# Battery_Board_v1.net
KiCad netlist of a schematic drawn in EAGLE
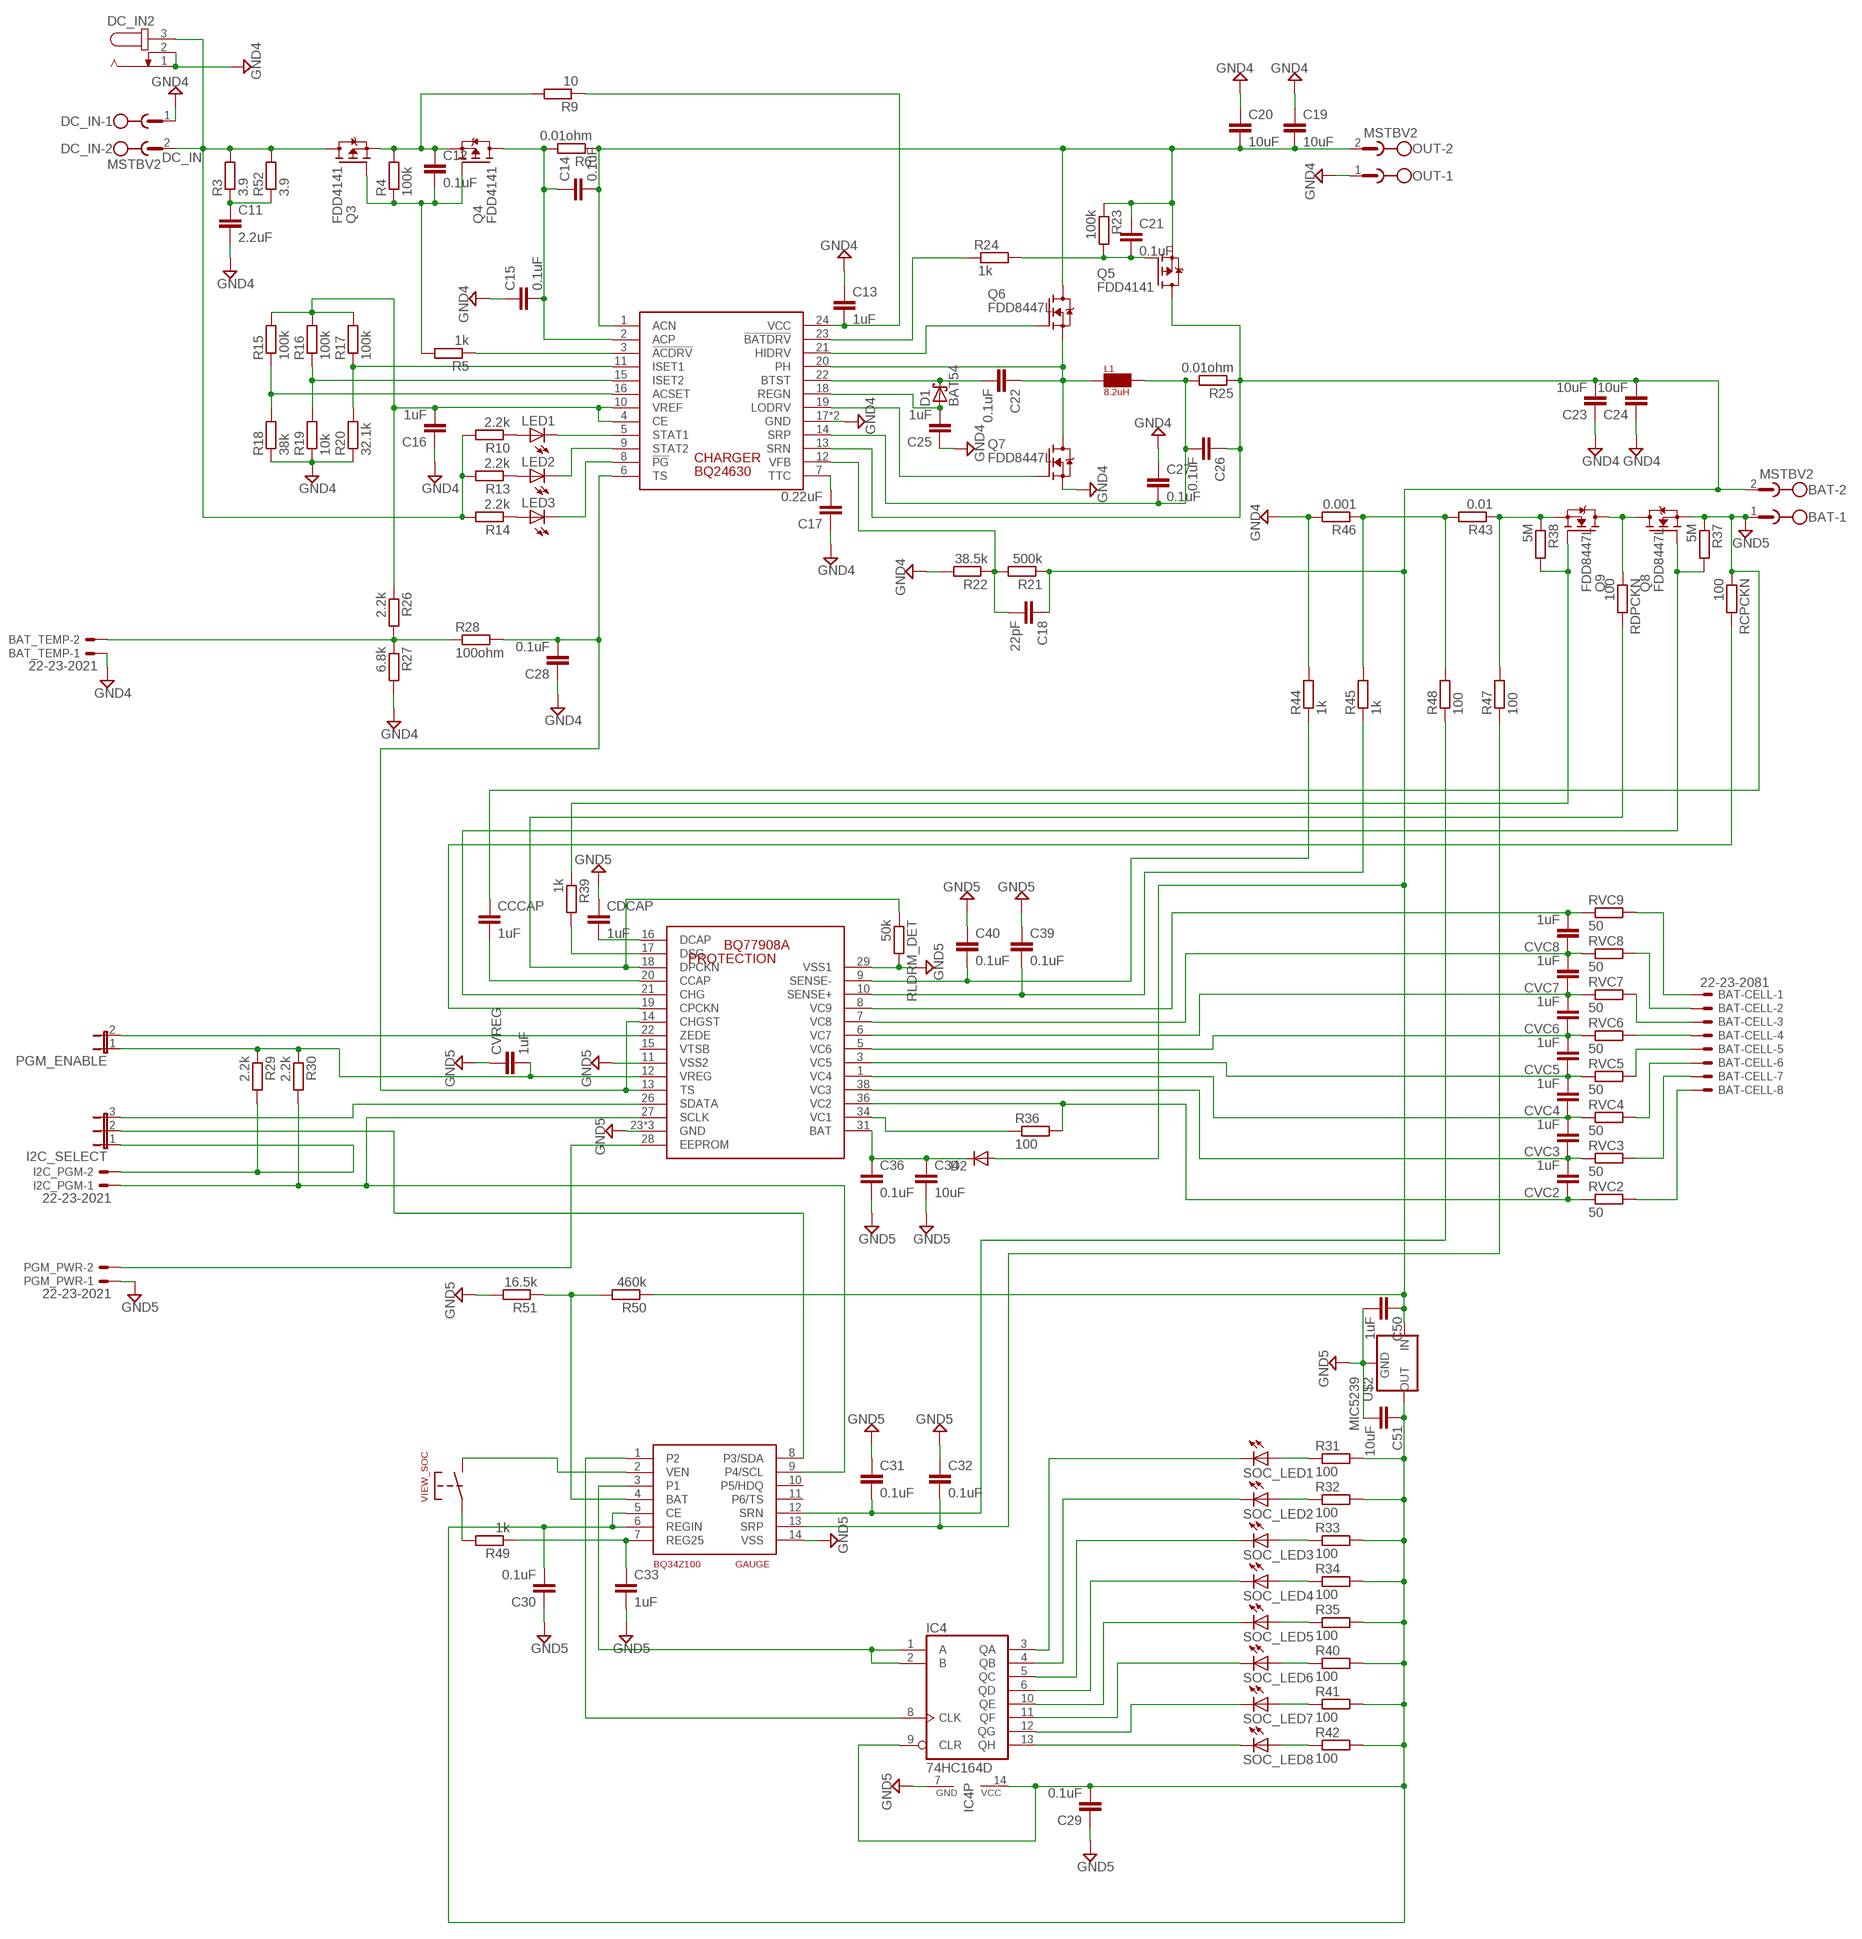
[diagram p0: schematic, sheet 1]

(export (version "E")
  (design (tool "Eeschema 10.0.6"))
  (components
    (comp (ref "BAT")
      (value "MSTBV2")
      (footprint "eagle-import:MSTBV2")
      (fields
        (field (name "MPN") "MSTBV 2,5/2-GF-5.08")
        (field (name "MPN_1") "MSTBV 2,5/2-GF-5.08")
        (field (name "OC_FARNELL") "1792792")
        (field (name "OC_NEWARK") "69R9845")
      )
      (libsource (lib "eagle-import") (part "MSTBV2"))
    )
    (comp (ref "BAT-CELL")
      (value "22-23-2081")
      (footprint "eagle-import:22-23-2081")
      (fields (field (name "MF") "MOLEX"))
      (libsource (lib "eagle-import") (part "22-23-2081"))
    )
    (comp (ref "BAT_TEMP")
      (value "22-23-2021")
      (footprint "eagle-import:22-23-2021")
      (fields
        (field (name "MF") "MOLEX")
        (field (name "MF_1") "MOLEX")
        (field (name "MPN") "22-23-2021")
        (field (name "OC_FARNELL") "1462926")
        (field (name "OC_NEWARK") "25C3832")
      )
      (libsource (lib "eagle-import") (part "22-23-2021"))
    )
    (comp (ref "C11")
      (value "2.2uF")
      (footprint "eagle-import:C1206")
      (libsource (lib "eagle-import") (part "C-EUC1206"))
    )
    (comp (ref "C12")
      (value "0.1uF")
      (footprint "eagle-import:C0603")
      (libsource (lib "eagle-import") (part "C-EUC0603"))
    )
    (comp (ref "C13")
      (value "1uF")
      (footprint "eagle-import:C1206")
      (libsource (lib "eagle-import") (part "C-EUC1206"))
    )
    (comp (ref "C14")
      (value "0.1uF")
      (footprint "eagle-import:C0603")
      (libsource (lib "eagle-import") (part "C-EUC0603"))
    )
    (comp (ref "C15")
      (value "0.1uF")
      (footprint "eagle-import:C0603")
      (libsource (lib "eagle-import") (part "C-EUC0603"))
    )
    (comp (ref "C16")
      (value "1uF")
      (footprint "eagle-import:C0805")
      (libsource (lib "eagle-import") (part "C-EUC0805"))
    )
    (comp (ref "C17")
      (value "0.22uF")
      (footprint "eagle-import:C0603")
      (libsource (lib "eagle-import") (part "C-EUC0603"))
    )
    (comp (ref "C18")
      (value "22pF")
      (footprint "eagle-import:C0603")
      (libsource (lib "eagle-import") (part "C-EUC0603"))
    )
    (comp (ref "C19")
      (value "10uF")
      (footprint "eagle-import:C1812")
      (libsource (lib "eagle-import") (part "C-EUC1812"))
    )
    (comp (ref "C20")
      (value "10uF")
      (footprint "eagle-import:C1812")
      (libsource (lib "eagle-import") (part "C-EUC1812"))
    )
    (comp (ref "C21")
      (value "0.1uF")
      (footprint "eagle-import:C0603")
      (libsource (lib "eagle-import") (part "C-EUC0603"))
    )
    (comp (ref "C22")
      (value "0.1uF")
      (footprint "eagle-import:C0603")
      (libsource (lib "eagle-import") (part "C-EUC0603"))
    )
    (comp (ref "C23")
      (value "10uF")
      (footprint "eagle-import:C1812")
      (libsource (lib "eagle-import") (part "C-EUC1812"))
    )
    (comp (ref "C24")
      (value "10uF")
      (footprint "eagle-import:C1812")
      (libsource (lib "eagle-import") (part "C-EUC1812"))
    )
    (comp (ref "C25")
      (value "1uF")
      (footprint "eagle-import:C0805")
      (libsource (lib "eagle-import") (part "C-EUC0805"))
    )
    (comp (ref "C26")
      (value "0.1uF")
      (footprint "eagle-import:C0603")
      (libsource (lib "eagle-import") (part "C-EUC0603"))
    )
    (comp (ref "C27")
      (value "0.1uF")
      (footprint "eagle-import:C0603")
      (libsource (lib "eagle-import") (part "C-EUC0603"))
    )
    (comp (ref "C28")
      (value "0.1uF")
      (footprint "eagle-import:C0603")
      (libsource (lib "eagle-import") (part "C-EUC0603"))
    )
    (comp (ref "C29")
      (value "0.1uF")
      (footprint "eagle-import:C0603")
      (libsource (lib "eagle-import") (part "C-EUC0603"))
    )
    (comp (ref "C30")
      (value "0.1uF")
      (footprint "eagle-import:C0603")
      (libsource (lib "eagle-import") (part "C-EUC0603"))
    )
    (comp (ref "C31")
      (value "0.1uF")
      (footprint "eagle-import:C0603")
      (libsource (lib "eagle-import") (part "C-EUC0603"))
    )
    (comp (ref "C32")
      (value "0.1uF")
      (footprint "eagle-import:C0603")
      (libsource (lib "eagle-import") (part "C-EUC0603"))
    )
    (comp (ref "C33")
      (value "1uF")
      (footprint "eagle-import:C0603")
      (libsource (lib "eagle-import") (part "C-EUC0603"))
    )
    (comp (ref "C34")
      (value "10uF")
      (footprint "eagle-import:C1210")
      (libsource (lib "eagle-import") (part "C-EUC1210"))
    )
    (comp (ref "C36")
      (value "0.1uF")
      (footprint "eagle-import:C1210")
      (libsource (lib "eagle-import") (part "C-EUC1210"))
    )
    (comp (ref "C39")
      (value "0.1uF")
      (footprint "eagle-import:C0603")
      (libsource (lib "eagle-import") (part "C-EUC0603"))
    )
    (comp (ref "C40")
      (value "0.1uF")
      (footprint "eagle-import:C0603")
      (libsource (lib "eagle-import") (part "C-EUC0603"))
    )
    (comp (ref "C50")
      (value "1uF")
      (footprint "eagle-import:C0603")
      (libsource (lib "eagle-import") (part "C-EUC0603"))
    )
    (comp (ref "C51")
      (value "10uF")
      (footprint "eagle-import:C0603")
      (libsource (lib "eagle-import") (part "C-EUC0603"))
    )
    (comp (ref "CCCAP")
      (value "1uF")
      (footprint "eagle-import:C1206")
      (libsource (lib "eagle-import") (part "C-EUC1206"))
    )
    (comp (ref "CDCAP")
      (value "1uF")
      (footprint "eagle-import:C1206")
      (libsource (lib "eagle-import") (part "C-EUC1206"))
    )
    (comp (ref "CHARGER")
      (value "BQ24630")
      (footprint "eagle-import:QFN-24")
      (libsource (lib "eagle-import") (part "BQ24630"))
    )
    (comp (ref "CVC2")
      (value "1uF")
      (footprint "eagle-import:C0603")
      (libsource (lib "eagle-import") (part "C-EUC0603"))
    )
    (comp (ref "CVC3")
      (value "1uF")
      (footprint "eagle-import:C0603")
      (libsource (lib "eagle-import") (part "C-EUC0603"))
    )
    (comp (ref "CVC4")
      (value "1uF")
      (footprint "eagle-import:C0603")
      (libsource (lib "eagle-import") (part "C-EUC0603"))
    )
    (comp (ref "CVC5")
      (value "1uF")
      (footprint "eagle-import:C0603")
      (libsource (lib "eagle-import") (part "C-EUC0603"))
    )
    (comp (ref "CVC6")
      (value "1uF")
      (footprint "eagle-import:C0603")
      (libsource (lib "eagle-import") (part "C-EUC0603"))
    )
    (comp (ref "CVC7")
      (value "1uF")
      (footprint "eagle-import:C0603")
      (libsource (lib "eagle-import") (part "C-EUC0603"))
    )
    (comp (ref "CVC8")
      (value "1uF")
      (footprint "eagle-import:C0603")
      (libsource (lib "eagle-import") (part "C-EUC0603"))
    )
    (comp (ref "CVREG")
      (value "1uF")
      (footprint "eagle-import:C0603")
      (libsource (lib "eagle-import") (part "C-EUC0603"))
    )
    (comp (ref "D1")
      (value "BAT54")
      (footprint "eagle-import:SOT23")
      (libsource (lib "eagle-import") (part "BAT54"))
    )
    (comp (ref "D2")
      (value "DIODE-SOD123")
      (footprint "eagle-import:SOD123")
      (libsource (lib "eagle-import") (part "DIODE-SOD123"))
    )
    (comp (ref "DC_IN")
      (value "MSTBV2")
      (footprint "eagle-import:MSTBV2")
      (fields (field (name "MPN") "MSTBV 2,5/2-GF-5.08"))
      (libsource (lib "eagle-import") (part "MSTBV2"))
    )
    (comp (ref "DC_IN2")
      (value "JACK-PLUG1")
      (footprint "eagle-import:SPC4078")
      (libsource (lib "eagle-import") (part "JACK-PLUG1"))
    )
    (comp (ref "GAUGE")
      (value "BQ34Z100")
      (footprint "eagle-import:TSSOP-14-0.65MM")
      (libsource (lib "eagle-import") (part "BQ34Z100"))
    )
    (comp (ref "I2C_PGM")
      (value "22-23-2021")
      (footprint "eagle-import:22-23-2021")
      (fields
        (field (name "MF") "MOLEX")
        (field (name "MF_1") "MOLEX")
        (field (name "MPN") "22-23-2021")
        (field (name "OC_FARNELL") "1462926")
        (field (name "OC_NEWARK") "25C3832")
      )
      (libsource (lib "eagle-import") (part "22-23-2021"))
    )
    (comp (ref "I2C_SELECT")
      (value "JP2E")
      (footprint "eagle-import:JP2")
      (libsource (lib "eagle-import") (part "JP2E"))
    )
    (comp (ref "IC4")
      (value "74HC164D")
      (footprint "eagle-import:SO14")
      (libsource (lib "eagle-import") (part "74164DHC"))
    )
    (comp (ref "L1")
      (value "8.2uH")
      (footprint "eagle-import:5050CE")
      (libsource (lib "eagle-import") (part "IHLP-5050CE"))
    )
    (comp (ref "LED1")
      (value "LEDCHIP-LED0603")
      (footprint "eagle-import:CHIP-LED0603")
      (libsource (lib "eagle-import") (part "LEDCHIP-LED0603"))
    )
    (comp (ref "LED2")
      (value "LEDCHIP-LED0603")
      (footprint "eagle-import:CHIP-LED0603")
      (libsource (lib "eagle-import") (part "LEDCHIP-LED0603"))
    )
    (comp (ref "LED3")
      (value "LEDCHIP-LED0603")
      (footprint "eagle-import:CHIP-LED0603")
      (libsource (lib "eagle-import") (part "LEDCHIP-LED0603"))
    )
    (comp (ref "OUT")
      (value "MSTBV2")
      (footprint "eagle-import:MSTBV2")
      (fields
        (field (name "MPN") "MSTBV 2,5/2-GF-5.08")
        (field (name "MPN_1") "MSTBV 2,5/2-GF-5.08")
        (field (name "OC_FARNELL") "1792792")
        (field (name "OC_NEWARK") "69R9845")
      )
      (libsource (lib "eagle-import") (part "MSTBV2"))
    )
    (comp (ref "PGM_ENABLE")
      (value "JP1E")
      (footprint "eagle-import:JP1")
      (libsource (lib "eagle-import") (part "JP1E"))
    )
    (comp (ref "PGM_PWR")
      (value "22-23-2021")
      (footprint "eagle-import:22-23-2021")
      (fields
        (field (name "MF") "MOLEX")
        (field (name "MF_1") "MOLEX")
        (field (name "MPN") "22-23-2021")
        (field (name "OC_FARNELL") "1462926")
        (field (name "OC_NEWARK") "25C3832")
      )
      (libsource (lib "eagle-import") (part "22-23-2021"))
    )
    (comp (ref "PROTECTION")
      (value "BQ77908A")
      (footprint "eagle-import:TSSOP-38-0.5MM")
      (libsource (lib "eagle-import") (part "BQ77908A"))
    )
    (comp (ref "Q3")
      (value "FDD4141")
      (footprint "eagle-import:TO252")
      (libsource (lib "eagle-import") (part "FDD4141TO252"))
    )
    (comp (ref "Q4")
      (value "FDD4141")
      (footprint "eagle-import:TO252")
      (libsource (lib "eagle-import") (part "FDD4141TO252"))
    )
    (comp (ref "Q5")
      (value "FDD4141")
      (footprint "eagle-import:TO252")
      (libsource (lib "eagle-import") (part "FDD4141TO252"))
    )
    (comp (ref "Q6")
      (value "FDD8447L")
      (footprint "eagle-import:TO252")
      (libsource (lib "eagle-import") (part "FDD8447L"))
    )
    (comp (ref "Q7")
      (value "FDD8447L")
      (footprint "eagle-import:TO252")
      (libsource (lib "eagle-import") (part "FDD8447L"))
    )
    (comp (ref "Q8")
      (value "FDD8447L")
      (footprint "eagle-import:TO252")
      (libsource (lib "eagle-import") (part "FDD8447L"))
    )
    (comp (ref "Q9")
      (value "FDD8447L")
      (footprint "eagle-import:TO252")
      (libsource (lib "eagle-import") (part "FDD8447L"))
    )
    (comp (ref "R3")
      (value "3.9")
      (footprint "eagle-import:R1206")
      (libsource (lib "eagle-import") (part "R-EU_R1206"))
    )
    (comp (ref "R4")
      (value "100k")
      (footprint "eagle-import:R0603")
      (libsource (lib "eagle-import") (part "R-EU_R0603"))
    )
    (comp (ref "R5")
      (value "1k")
      (footprint "eagle-import:R0603")
      (libsource (lib "eagle-import") (part "R-EU_R0603"))
    )
    (comp (ref "R6")
      (value "0.01ohm")
      (footprint "eagle-import:R2010")
      (libsource (lib "eagle-import") (part "R-EU_R2010"))
    )
    (comp (ref "R9")
      (value "10")
      (footprint "eagle-import:R1206")
      (libsource (lib "eagle-import") (part "R-EU_R1206"))
    )
    (comp (ref "R10")
      (value "2.2k")
      (footprint "eagle-import:R0603")
      (libsource (lib "eagle-import") (part "R-EU_R0603"))
    )
    (comp (ref "R13")
      (value "2.2k")
      (footprint "eagle-import:R0603")
      (libsource (lib "eagle-import") (part "R-EU_R0603"))
    )
    (comp (ref "R14")
      (value "2.2k")
      (footprint "eagle-import:R0603")
      (libsource (lib "eagle-import") (part "R-EU_R0603"))
    )
    (comp (ref "R15")
      (value "100k")
      (footprint "eagle-import:R0805")
      (libsource (lib "eagle-import") (part "R-EU_R0805"))
    )
    (comp (ref "R16")
      (value "100k")
      (footprint "eagle-import:R0805")
      (libsource (lib "eagle-import") (part "R-EU_R0805"))
    )
    (comp (ref "R17")
      (value "100k")
      (footprint "eagle-import:R0805")
      (libsource (lib "eagle-import") (part "R-EU_R0805"))
    )
    (comp (ref "R18")
      (value "38k")
      (footprint "eagle-import:R0805")
      (libsource (lib "eagle-import") (part "R-EU_R0805"))
    )
    (comp (ref "R19")
      (value "10k")
      (footprint "eagle-import:R0805")
      (libsource (lib "eagle-import") (part "R-EU_R0805"))
    )
    (comp (ref "R20")
      (value "32.1k")
      (footprint "eagle-import:R0805")
      (libsource (lib "eagle-import") (part "R-EU_R0805"))
    )
    (comp (ref "R21")
      (value "500k")
      (footprint "eagle-import:R0805")
      (libsource (lib "eagle-import") (part "R-EU_R0805"))
    )
    (comp (ref "R22")
      (value "38.5k")
      (footprint "eagle-import:R0805")
      (libsource (lib "eagle-import") (part "R-EU_R0805"))
    )
    (comp (ref "R23")
      (value "100k")
      (footprint "eagle-import:R0603")
      (libsource (lib "eagle-import") (part "R-EU_R0603"))
    )
    (comp (ref "R24")
      (value "1k")
      (footprint "eagle-import:R0603")
      (libsource (lib "eagle-import") (part "R-EU_R0603"))
    )
    (comp (ref "R25")
      (value "0.01ohm")
      (footprint "eagle-import:R2010")
      (libsource (lib "eagle-import") (part "R-EU_R2010"))
    )
    (comp (ref "R26")
      (value "2.2k")
      (footprint "eagle-import:R0603")
      (libsource (lib "eagle-import") (part "R-EU_R0603"))
    )
    (comp (ref "R27")
      (value "6.8k")
      (footprint "eagle-import:R0603")
      (libsource (lib "eagle-import") (part "R-EU_R0603"))
    )
    (comp (ref "R28")
      (value "100ohm")
      (footprint "eagle-import:R0603")
      (libsource (lib "eagle-import") (part "R-EU_R0603"))
    )
    (comp (ref "R29")
      (value "2.2k")
      (footprint "eagle-import:R0603")
      (libsource (lib "eagle-import") (part "R-EU_R0603"))
    )
    (comp (ref "R30")
      (value "2.2k")
      (footprint "eagle-import:R0603")
      (libsource (lib "eagle-import") (part "R-EU_R0603"))
    )
    (comp (ref "R31")
      (value "100")
      (footprint "eagle-import:R0603")
      (libsource (lib "eagle-import") (part "R-EU_R0603"))
    )
    (comp (ref "R32")
      (value "100")
      (footprint "eagle-import:R0603")
      (libsource (lib "eagle-import") (part "R-EU_R0603"))
    )
    (comp (ref "R33")
      (value "100")
      (footprint "eagle-import:R0603")
      (libsource (lib "eagle-import") (part "R-EU_R0603"))
    )
    (comp (ref "R34")
      (value "100")
      (footprint "eagle-import:R0603")
      (libsource (lib "eagle-import") (part "R-EU_R0603"))
    )
    (comp (ref "R35")
      (value "100")
      (footprint "eagle-import:R0603")
      (libsource (lib "eagle-import") (part "R-EU_R0603"))
    )
    (comp (ref "R36")
      (value "100")
      (footprint "eagle-import:R0603")
      (libsource (lib "eagle-import") (part "R-EU_R0603"))
    )
    (comp (ref "R37")
      (value "5M")
      (footprint "eagle-import:R0603")
      (libsource (lib "eagle-import") (part "R-EU_R0603"))
    )
    (comp (ref "R38")
      (value "5M")
      (footprint "eagle-import:R0603")
      (libsource (lib "eagle-import") (part "R-EU_R0603"))
    )
    (comp (ref "R39")
      (value "1k")
      (footprint "eagle-import:R0603")
      (libsource (lib "eagle-import") (part "R-EU_R0603"))
    )
    (comp (ref "R40")
      (value "100")
      (footprint "eagle-import:R0603")
      (libsource (lib "eagle-import") (part "R-EU_R0603"))
    )
    (comp (ref "R41")
      (value "100")
      (footprint "eagle-import:R0603")
      (libsource (lib "eagle-import") (part "R-EU_R0603"))
    )
    (comp (ref "R42")
      (value "100")
      (footprint "eagle-import:R0603")
      (libsource (lib "eagle-import") (part "R-EU_R0603"))
    )
    (comp (ref "R43")
      (value "0.01")
      (footprint "eagle-import:R2010")
      (libsource (lib "eagle-import") (part "R-EU_R2010"))
    )
    (comp (ref "R44")
      (value "1k")
      (footprint "eagle-import:R0603")
      (libsource (lib "eagle-import") (part "R-EU_R0603"))
    )
    (comp (ref "R45")
      (value "1k")
      (footprint "eagle-import:R0603")
      (libsource (lib "eagle-import") (part "R-EU_R0603"))
    )
    (comp (ref "R46")
      (value "0.001")
      (footprint "eagle-import:R2010")
      (libsource (lib "eagle-import") (part "R-EU_R2010"))
    )
    (comp (ref "R47")
      (value "100")
      (footprint "eagle-import:R0603")
      (libsource (lib "eagle-import") (part "R-EU_R0603"))
    )
    (comp (ref "R48")
      (value "100")
      (footprint "eagle-import:R0603")
      (libsource (lib "eagle-import") (part "R-EU_R0603"))
    )
    (comp (ref "R49")
      (value "1k")
      (footprint "eagle-import:R0603")
      (libsource (lib "eagle-import") (part "R-EU_R0603"))
    )
    (comp (ref "R50")
      (value "460k")
      (footprint "eagle-import:R0805")
      (libsource (lib "eagle-import") (part "R-EU_R0805"))
    )
    (comp (ref "R51")
      (value "16.5k")
      (footprint "eagle-import:R0603")
      (libsource (lib "eagle-import") (part "R-EU_R0603"))
    )
    (comp (ref "R52")
      (value "3.9")
      (footprint "eagle-import:R1206")
      (libsource (lib "eagle-import") (part "R-EU_R1206"))
    )
    (comp (ref "RCPCKN")
      (value "100")
      (footprint "eagle-import:R0603")
      (libsource (lib "eagle-import") (part "R-EU_R0603"))
    )
    (comp (ref "RDPCKN")
      (value "100")
      (footprint "eagle-import:R0603")
      (libsource (lib "eagle-import") (part "R-EU_R0603"))
    )
    (comp (ref "RLDRM_DET")
      (value "50k")
      (footprint "eagle-import:R0603")
      (libsource (lib "eagle-import") (part "R-EU_R0603"))
    )
    (comp (ref "RVC2")
      (value "50")
      (footprint "eagle-import:R1206")
      (libsource (lib "eagle-import") (part "R-EU_R1206"))
    )
    (comp (ref "RVC3")
      (value "50")
      (footprint "eagle-import:R1206")
      (libsource (lib "eagle-import") (part "R-EU_R1206"))
    )
    (comp (ref "RVC4")
      (value "50")
      (footprint "eagle-import:R1206")
      (libsource (lib "eagle-import") (part "R-EU_R1206"))
    )
    (comp (ref "RVC5")
      (value "50")
      (footprint "eagle-import:R1206")
      (libsource (lib "eagle-import") (part "R-EU_R1206"))
    )
    (comp (ref "RVC6")
      (value "50")
      (footprint "eagle-import:R1206")
      (libsource (lib "eagle-import") (part "R-EU_R1206"))
    )
    (comp (ref "RVC7")
      (value "50")
      (footprint "eagle-import:R1206")
      (libsource (lib "eagle-import") (part "R-EU_R1206"))
    )
    (comp (ref "RVC8")
      (value "50")
      (footprint "eagle-import:R1206")
      (libsource (lib "eagle-import") (part "R-EU_R1206"))
    )
    (comp (ref "RVC9")
      (value "50")
      (footprint "eagle-import:R1206")
      (libsource (lib "eagle-import") (part "R-EU_R1206"))
    )
    (comp (ref "SOC_LED1")
      (value "LEDCHIP-LED0603")
      (footprint "eagle-import:CHIP-LED0603")
      (libsource (lib "eagle-import") (part "LEDCHIP-LED0603"))
    )
    (comp (ref "SOC_LED2")
      (value "LEDCHIP-LED0603")
      (footprint "eagle-import:CHIP-LED0603")
      (libsource (lib "eagle-import") (part "LEDCHIP-LED0603"))
    )
    (comp (ref "SOC_LED3")
      (value "LEDCHIP-LED0603")
      (footprint "eagle-import:CHIP-LED0603")
      (libsource (lib "eagle-import") (part "LEDCHIP-LED0603"))
    )
    (comp (ref "SOC_LED4")
      (value "LEDCHIP-LED0603")
      (footprint "eagle-import:CHIP-LED0603")
      (libsource (lib "eagle-import") (part "LEDCHIP-LED0603"))
    )
    (comp (ref "SOC_LED5")
      (value "LEDCHIP-LED0603")
      (footprint "eagle-import:CHIP-LED0603")
      (libsource (lib "eagle-import") (part "LEDCHIP-LED0603"))
    )
    (comp (ref "SOC_LED6")
      (value "LEDCHIP-LED0603")
      (footprint "eagle-import:CHIP-LED0603")
      (libsource (lib "eagle-import") (part "LEDCHIP-LED0603"))
    )
    (comp (ref "SOC_LED7")
      (value "LEDCHIP-LED0603")
      (footprint "eagle-import:CHIP-LED0603")
      (libsource (lib "eagle-import") (part "LEDCHIP-LED0603"))
    )
    (comp (ref "SOC_LED8")
      (value "LEDCHIP-LED0603")
      (footprint "eagle-import:CHIP-LED0603")
      (libsource (lib "eagle-import") (part "LEDCHIP-LED0603"))
    )
    (comp (ref "U$2")
      (value "MIC5239")
      (footprint "eagle-import:SOT223")
      (libsource (lib "eagle-import") (part "MIC5239"))
    )
    (comp (ref "VIEW_SOC")
      (value "PUSHBUTTON")
      (footprint "eagle-import:PUSHBUTTON")
      (libsource (lib "eagle-import") (part "PUSHBUTTON"))
    )
  )
  (nets
    (net (code "1") (name "/DC_IN") (class "Default")
      (node (ref "DC_IN") (pin "2") (pinfunction "1_2") (pintype "passive"))
      (node (ref "DC_IN2") (pin "3") (pinfunction "3_3") (pintype "passive"))
      (node (ref "Q3") (pin "3") (pinfunction "D_3") (pintype "passive"))
      (node (ref "R10") (pin "2") (pinfunction "2_2") (pintype "passive"))
      (node (ref "R13") (pin "2") (pinfunction "2_2") (pintype "passive"))
      (node (ref "R14") (pin "2") (pinfunction "2_2") (pintype "passive"))
      (node (ref "R3") (pin "2") (pinfunction "2_2") (pintype "passive"))
      (node (ref "R52") (pin "2") (pinfunction "2_2") (pintype "passive"))
    )
    (net (code "2") (name "GND4") (class "Default")
      (node (ref "BAT_TEMP") (pin "1") (pinfunction "S_1") (pintype "passive"))
      (node (ref "C11") (pin "2") (pinfunction "2_2") (pintype "passive"))
      (node (ref "C13") (pin "1") (pinfunction "1_1") (pintype "passive"))
      (node (ref "C15") (pin "1") (pinfunction "1_1") (pintype "passive"))
      (node (ref "C16") (pin "1") (pinfunction "1_1") (pintype "passive"))
      (node (ref "C17") (pin "1") (pinfunction "1_1") (pintype "passive"))
      (node (ref "C19") (pin "1") (pinfunction "1_1") (pintype "passive"))
      (node (ref "C20") (pin "1") (pinfunction "1_1") (pintype "passive"))
      (node (ref "C23") (pin "1") (pinfunction "1_1") (pintype "passive"))
      (node (ref "C24") (pin "1") (pinfunction "1_1") (pintype "passive"))
      (node (ref "C25") (pin "1") (pinfunction "1_1") (pintype "passive"))
      (node (ref "C27") (pin "1") (pinfunction "1_1") (pintype "passive"))
      (node (ref "C28") (pin "1") (pinfunction "1_1") (pintype "passive"))
      (node (ref "CHARGER") (pin "17") (pinfunction "GND_17") (pintype "bidirectional"))
      (node (ref "CHARGER") (pin "THERMAL") (pinfunction "GND_THERMAL") (pintype "bidirectional"))
      (node (ref "DC_IN") (pin "1") (pinfunction "1_1") (pintype "passive"))
      (node (ref "DC_IN2") (pin "1") (pinfunction "1_1") (pintype "passive"))
      (node (ref "DC_IN2") (pin "2") (pinfunction "2_2") (pintype "passive"))
      (node (ref "OUT") (pin "1") (pinfunction "1_1") (pintype "passive"))
      (node (ref "Q7") (pin "2") (pinfunction "S_2") (pintype "passive"))
      (node (ref "R18") (pin "1") (pinfunction "1_1") (pintype "passive"))
      (node (ref "R19") (pin "1") (pinfunction "1_1") (pintype "passive"))
      (node (ref "R20") (pin "1") (pinfunction "1_1") (pintype "passive"))
      (node (ref "R22") (pin "2") (pinfunction "2_2") (pintype "passive"))
      (node (ref "R27") (pin "2") (pinfunction "2_2") (pintype "passive"))
      (node (ref "R44") (pin "2") (pinfunction "2_2") (pintype "passive"))
      (node (ref "R46") (pin "2") (pinfunction "2_2") (pintype "passive"))
    )
    (net (code "3") (name "GND5") (class "Default")
      (node (ref "BAT") (pin "1") (pinfunction "1_1") (pintype "passive"))
      (node (ref "C29") (pin "1") (pinfunction "1_1") (pintype "passive"))
      (node (ref "C30") (pin "1") (pinfunction "1_1") (pintype "passive"))
      (node (ref "C31") (pin "1") (pinfunction "1_1") (pintype "passive"))
      (node (ref "C32") (pin "1") (pinfunction "1_1") (pintype "passive"))
      (node (ref "C33") (pin "2") (pinfunction "2_2") (pintype "passive"))
      (node (ref "C34") (pin "2") (pinfunction "2_2") (pintype "passive"))
      (node (ref "C36") (pin "2") (pinfunction "2_2") (pintype "passive"))
      (node (ref "C39") (pin "1") (pinfunction "1_1") (pintype "passive"))
      (node (ref "C40") (pin "1") (pinfunction "1_1") (pintype "passive"))
      (node (ref "C50") (pin "2") (pinfunction "2_2") (pintype "passive"))
      (node (ref "C51") (pin "2") (pinfunction "2_2") (pintype "passive"))
      (node (ref "CCCAP") (pin "1") (pinfunction "1_1") (pintype "passive"))
      (node (ref "CDCAP") (pin "1") (pinfunction "1_1") (pintype "passive"))
      (node (ref "CVREG") (pin "1") (pinfunction "1_1") (pintype "passive"))
      (node (ref "GAUGE") (pin "14") (pinfunction "VSS_14") (pintype "bidirectional"))
      (node (ref "IC4") (pin "7") (pinfunction "GND_7") (pintype "power_in"))
      (node (ref "PGM_PWR") (pin "1") (pinfunction "S_1") (pintype "passive"))
      (node (ref "PROTECTION") (pin "11") (pinfunction "VSS2_11") (pintype "bidirectional"))
      (node (ref "PROTECTION") (pin "23") (pinfunction "GND_23") (pintype "bidirectional"))
      (node (ref "PROTECTION") (pin "24") (pinfunction "GND_24") (pintype "bidirectional"))
      (node (ref "PROTECTION") (pin "25") (pinfunction "GND_25") (pintype "bidirectional"))
      (node (ref "PROTECTION") (pin "29") (pinfunction "VSS1_29") (pintype "bidirectional"))
      (node (ref "Q8") (pin "2") (pinfunction "S_2") (pintype "passive"))
      (node (ref "R37") (pin "1") (pinfunction "1_1") (pintype "passive"))
      (node (ref "R51") (pin "2") (pinfunction "2_2") (pintype "passive"))
      (node (ref "RCPCKN") (pin "1") (pinfunction "1_1") (pintype "passive"))
      (node (ref "RLDRM_DET") (pin "2") (pinfunction "2_2") (pintype "passive"))
      (node (ref "U$2") (pin "2") (pinfunction "GND_2") (pintype "input"))
      (node (ref "U$2") (pin "4") (pinfunction "GND_4") (pintype "input"))
    )
    (net (code "4") (name "Net-(BAT-CELLA-S)") (class "Default")
      (node (ref "BAT-CELL") (pin "1") (pinfunction "S_1") (pintype "passive"))
      (node (ref "RVC9") (pin "2") (pinfunction "2_2") (pintype "passive"))
    )
    (net (code "5") (name "Net-(BAT-CELLB-S)") (class "Default")
      (node (ref "BAT-CELL") (pin "2") (pinfunction "S_2") (pintype "passive"))
      (node (ref "RVC8") (pin "2") (pinfunction "2_2") (pintype "passive"))
    )
    (net (code "6") (name "Net-(BAT-CELLC-S)") (class "Default")
      (node (ref "BAT-CELL") (pin "3") (pinfunction "S_3") (pintype "passive"))
      (node (ref "RVC7") (pin "2") (pinfunction "2_2") (pintype "passive"))
    )
    (net (code "7") (name "Net-(BAT-CELLD-S)") (class "Default")
      (node (ref "BAT-CELL") (pin "4") (pinfunction "S_4") (pintype "passive"))
      (node (ref "RVC6") (pin "2") (pinfunction "2_2") (pintype "passive"))
    )
    (net (code "8") (name "Net-(BAT-CELLE-S)") (class "Default")
      (node (ref "BAT-CELL") (pin "5") (pinfunction "S_5") (pintype "passive"))
      (node (ref "RVC5") (pin "2") (pinfunction "2_2") (pintype "passive"))
    )
    (net (code "9") (name "Net-(BAT-CELLF-S)") (class "Default")
      (node (ref "BAT-CELL") (pin "6") (pinfunction "S_6") (pintype "passive"))
      (node (ref "RVC4") (pin "2") (pinfunction "2_2") (pintype "passive"))
    )
    (net (code "10") (name "Net-(BAT-CELLG-S)") (class "Default")
      (node (ref "BAT-CELL") (pin "7") (pinfunction "S_7") (pintype "passive"))
      (node (ref "RVC3") (pin "2") (pinfunction "2_2") (pintype "passive"))
    )
    (net (code "11") (name "Net-(BAT-CELLH-S)") (class "Default")
      (node (ref "BAT-CELL") (pin "8") (pinfunction "S_8") (pintype "passive"))
      (node (ref "RVC2") (pin "2") (pinfunction "2_2") (pintype "passive"))
    )
    (net (code "12") (name "Net-(BATB-1)") (class "Default")
      (node (ref "BAT") (pin "2") (pinfunction "1_2") (pintype "passive"))
      (node (ref "C18") (pin "1") (pinfunction "1_1") (pintype "passive"))
      (node (ref "C23") (pin "2") (pinfunction "2_2") (pintype "passive"))
      (node (ref "C24") (pin "2") (pinfunction "2_2") (pintype "passive"))
      (node (ref "C26") (pin "1") (pinfunction "1_1") (pintype "passive"))
      (node (ref "C50") (pin "1") (pinfunction "1_1") (pintype "passive"))
      (node (ref "CHARGER") (pin "13") (pinfunction "SRN_13") (pintype "bidirectional"))
      (node (ref "D2") (pin "A") (pinfunction "A_A") (pintype "passive"))
      (node (ref "Q5") (pin "3") (pinfunction "D_3") (pintype "passive"))
      (node (ref "R21") (pin "1") (pinfunction "1_1") (pintype "passive"))
      (node (ref "R25") (pin "1") (pinfunction "1_1") (pintype "passive"))
      (node (ref "R50") (pin "1") (pinfunction "1_1") (pintype "passive"))
      (node (ref "U$2") (pin "1") (pinfunction "IN_1") (pintype "input"))
    )
    (net (code "13") (name "Net-(BAT_TEMPB-S)") (class "Default")
      (node (ref "BAT_TEMP") (pin "2") (pinfunction "S_2") (pintype "passive"))
      (node (ref "R26") (pin "2") (pinfunction "2_2") (pintype "passive"))
      (node (ref "R27") (pin "1") (pinfunction "1_1") (pintype "passive"))
      (node (ref "R28") (pin "1") (pinfunction "1_1") (pintype "passive"))
    )
    (net (code "14") (name "Net-(C11-Pad1)") (class "Default")
      (node (ref "C11") (pin "1") (pinfunction "1_1") (pintype "passive"))
      (node (ref "R3") (pin "1") (pinfunction "1_1") (pintype "passive"))
      (node (ref "R52") (pin "1") (pinfunction "1_1") (pintype "passive"))
    )
    (net (code "15") (name "Net-(CHARGER-ACN)") (class "Default")
      (node (ref "C14") (pin "2") (pinfunction "2_2") (pintype "passive"))
      (node (ref "C19") (pin "2") (pinfunction "2_2") (pintype "passive"))
      (node (ref "C20") (pin "2") (pinfunction "2_2") (pintype "passive"))
      (node (ref "C21") (pin "1") (pinfunction "1_1") (pintype "passive"))
      (node (ref "CHARGER") (pin "1") (pinfunction "ACN_1") (pintype "bidirectional"))
      (node (ref "OUT") (pin "2") (pinfunction "1_2") (pintype "passive"))
      (node (ref "Q5") (pin "2") (pinfunction "S_2") (pintype "passive"))
      (node (ref "Q6") (pin "3") (pinfunction "D_3") (pintype "passive"))
      (node (ref "R23") (pin "1") (pinfunction "1_1") (pintype "passive"))
      (node (ref "R6") (pin "1") (pinfunction "1_1") (pintype "passive"))
    )
    (net (code "16") (name "Net-(CHARGER-ACP)") (class "Default")
      (node (ref "C14") (pin "1") (pinfunction "1_1") (pintype "passive"))
      (node (ref "C15") (pin "2") (pinfunction "2_2") (pintype "passive"))
      (node (ref "CHARGER") (pin "2") (pinfunction "ACP_2") (pintype "bidirectional"))
      (node (ref "Q4") (pin "3") (pinfunction "D_3") (pintype "passive"))
      (node (ref "R6") (pin "2") (pinfunction "2_2") (pintype "passive"))
    )
    (net (code "17") (name "Net-(CHARGER-ACSET)") (class "Default")
      (node (ref "CHARGER") (pin "16") (pinfunction "ACSET_16") (pintype "bidirectional"))
      (node (ref "R15") (pin "1") (pinfunction "1_1") (pintype "passive"))
      (node (ref "R18") (pin "2") (pinfunction "2_2") (pintype "passive"))
    )
    (net (code "18") (name "Net-(CHARGER-BTST)") (class "Default")
      (node (ref "C22") (pin "2") (pinfunction "2_2") (pintype "passive"))
      (node (ref "CHARGER") (pin "22") (pinfunction "BTST_22") (pintype "bidirectional"))
      (node (ref "D1") (pin "3") (pinfunction "C_3") (pintype "passive"))
    )
    (net (code "19") (name "Net-(CHARGER-CE)") (class "Default")
      (node (ref "C16") (pin "2") (pinfunction "2_2") (pintype "passive"))
      (node (ref "CHARGER") (pin "10") (pinfunction "VREF_10") (pintype "bidirectional"))
      (node (ref "CHARGER") (pin "4") (pinfunction "CE_4") (pintype "bidirectional"))
      (node (ref "R15") (pin "2") (pinfunction "2_2") (pintype "passive"))
      (node (ref "R16") (pin "2") (pinfunction "2_2") (pintype "passive"))
      (node (ref "R17") (pin "2") (pinfunction "2_2") (pintype "passive"))
      (node (ref "R26") (pin "1") (pinfunction "1_1") (pintype "passive"))
    )
    (net (code "20") (name "Net-(CHARGER-HIDRV)") (class "Default")
      (node (ref "CHARGER") (pin "21") (pinfunction "HIDRV_21") (pintype "bidirectional"))
      (node (ref "Q6") (pin "1") (pinfunction "G_1") (pintype "passive"))
    )
    (net (code "21") (name "Net-(CHARGER-ISET1)") (class "Default")
      (node (ref "CHARGER") (pin "11") (pinfunction "ISET1_11") (pintype "bidirectional"))
      (node (ref "R17") (pin "1") (pinfunction "1_1") (pintype "passive"))
      (node (ref "R20") (pin "2") (pinfunction "2_2") (pintype "passive"))
    )
    (net (code "22") (name "Net-(CHARGER-ISET2)") (class "Default")
      (node (ref "CHARGER") (pin "15") (pinfunction "ISET2_15") (pintype "bidirectional"))
      (node (ref "R16") (pin "1") (pinfunction "1_1") (pintype "passive"))
      (node (ref "R19") (pin "2") (pinfunction "2_2") (pintype "passive"))
    )
    (net (code "23") (name "Net-(CHARGER-LODRV)") (class "Default")
      (node (ref "CHARGER") (pin "19") (pinfunction "LODRV_19") (pintype "bidirectional"))
      (node (ref "Q7") (pin "1") (pinfunction "G_1") (pintype "passive"))
    )
    (net (code "24") (name "Net-(CHARGER-PH)") (class "Default")
      (node (ref "C22") (pin "1") (pinfunction "1_1") (pintype "passive"))
      (node (ref "CHARGER") (pin "20") (pinfunction "PH_20") (pintype "bidirectional"))
      (node (ref "L1") (pin "P$1") (pinfunction "P$1_P$1") (pintype "bidirectional"))
      (node (ref "Q6") (pin "2") (pinfunction "S_2") (pintype "passive"))
      (node (ref "Q7") (pin "3") (pinfunction "D_3") (pintype "passive"))
    )
    (net (code "25") (name "Net-(CHARGER-REGN)") (class "Default")
      (node (ref "C25") (pin "2") (pinfunction "2_2") (pintype "passive"))
      (node (ref "CHARGER") (pin "18") (pinfunction "REGN_18") (pintype "bidirectional"))
      (node (ref "D1") (pin "1") (pinfunction "A_1") (pintype "passive"))
    )
    (net (code "26") (name "Net-(CHARGER-SRP)") (class "Default")
      (node (ref "C26") (pin "2") (pinfunction "2_2") (pintype "passive"))
      (node (ref "C27") (pin "2") (pinfunction "2_2") (pintype "passive"))
      (node (ref "CHARGER") (pin "14") (pinfunction "SRP_14") (pintype "bidirectional"))
      (node (ref "L1") (pin "P$2") (pinfunction "P$2_P$2") (pintype "bidirectional"))
      (node (ref "R25") (pin "2") (pinfunction "2_2") (pintype "passive"))
    )
    (net (code "27") (name "Net-(CHARGER-STAT1)") (class "Default")
      (node (ref "CHARGER") (pin "5") (pinfunction "STAT1_5") (pintype "bidirectional"))
      (node (ref "LED1") (pin "C") (pinfunction "C_C") (pintype "passive"))
    )
    (net (code "28") (name "Net-(CHARGER-STAT2)") (class "Default")
      (node (ref "CHARGER") (pin "9") (pinfunction "STAT2_9") (pintype "bidirectional"))
      (node (ref "LED2") (pin "C") (pinfunction "C_C") (pintype "passive"))
    )
    (net (code "29") (name "Net-(CHARGER-TS)") (class "Default")
      (node (ref "C28") (pin "2") (pinfunction "2_2") (pintype "passive"))
      (node (ref "CHARGER") (pin "6") (pinfunction "TS_6") (pintype "bidirectional"))
      (node (ref "PROTECTION") (pin "13") (pinfunction "TS_13") (pintype "bidirectional"))
      (node (ref "PROTECTION") (pin "14") (pinfunction "CHGST_14") (pintype "bidirectional"))
      (node (ref "R28") (pin "2") (pinfunction "2_2") (pintype "passive"))
    )
    (net (code "30") (name "Net-(CHARGER-TTC)") (class "Default")
      (node (ref "C17") (pin "2") (pinfunction "2_2") (pintype "passive"))
      (node (ref "CHARGER") (pin "7") (pinfunction "TTC_7") (pintype "bidirectional"))
    )
    (net (code "31") (name "Net-(CHARGER-VCC)") (class "Default")
      (node (ref "C13") (pin "2") (pinfunction "2_2") (pintype "passive"))
      (node (ref "CHARGER") (pin "24") (pinfunction "VCC_24") (pintype "bidirectional"))
      (node (ref "R9") (pin "1") (pinfunction "1_1") (pintype "passive"))
    )
    (net (code "32") (name "Net-(CHARGER-VFB)") (class "Default")
      (node (ref "C18") (pin "2") (pinfunction "2_2") (pintype "passive"))
      (node (ref "CHARGER") (pin "12") (pinfunction "VFB_12") (pintype "bidirectional"))
      (node (ref "R21") (pin "2") (pinfunction "2_2") (pintype "passive"))
      (node (ref "R22") (pin "1") (pinfunction "1_1") (pintype "passive"))
    )
    (net (code "33") (name "Net-(CHARGER-~{ACDRV})") (class "Default")
      (node (ref "CHARGER") (pin "3") (pinfunction "~{ACDRV}_3") (pintype "bidirectional"))
      (node (ref "R5") (pin "1") (pinfunction "1_1") (pintype "passive"))
    )
    (net (code "34") (name "Net-(CHARGER-~{BATDRV})") (class "Default")
      (node (ref "CHARGER") (pin "23") (pinfunction "~{BATDRV}_23") (pintype "bidirectional"))
      (node (ref "R24") (pin "1") (pinfunction "1_1") (pintype "passive"))
    )
    (net (code "35") (name "Net-(CHARGER-~{PG})") (class "Default")
      (node (ref "CHARGER") (pin "8") (pinfunction "~{PG}_8") (pintype "bidirectional"))
      (node (ref "LED3") (pin "C") (pinfunction "C_C") (pintype "passive"))
    )
    (net (code "36") (name "Net-(GAUGE-BAT)") (class "Default")
      (node (ref "GAUGE") (pin "4") (pinfunction "BAT_4") (pintype "bidirectional"))
      (node (ref "R50") (pin "2") (pinfunction "2_2") (pintype "passive"))
      (node (ref "R51") (pin "1") (pinfunction "1_1") (pintype "passive"))
    )
    (net (code "37") (name "Net-(GAUGE-CE)") (class "Default")
      (node (ref "C29") (pin "2") (pinfunction "2_2") (pintype "passive"))
      (node (ref "C30") (pin "2") (pinfunction "2_2") (pintype "passive"))
      (node (ref "C51") (pin "1") (pinfunction "1_1") (pintype "passive"))
      (node (ref "GAUGE") (pin "5") (pinfunction "CE_5") (pintype "bidirectional"))
      (node (ref "GAUGE") (pin "6") (pinfunction "REGIN_6") (pintype "bidirectional"))
      (node (ref "IC4") (pin "14") (pinfunction "VCC_14") (pintype "power_in"))
      (node (ref "IC4") (pin "9") (pinfunction "CLR_9") (pintype "input"))
      (node (ref "R31") (pin "2") (pinfunction "2_2") (pintype "passive"))
      (node (ref "R32") (pin "2") (pinfunction "2_2") (pintype "passive"))
      (node (ref "R33") (pin "2") (pinfunction "2_2") (pintype "passive"))
      (node (ref "R34") (pin "2") (pinfunction "2_2") (pintype "passive"))
      (node (ref "R35") (pin "2") (pinfunction "2_2") (pintype "passive"))
      (node (ref "R40") (pin "2") (pinfunction "2_2") (pintype "passive"))
      (node (ref "R41") (pin "2") (pinfunction "2_2") (pintype "passive"))
      (node (ref "R42") (pin "2") (pinfunction "2_2") (pintype "passive"))
      (node (ref "U$2") (pin "3") (pinfunction "OUT_3") (pintype "passive"))
    )
    (net (code "38") (name "Net-(GAUGE-P1)") (class "Default")
      (node (ref "GAUGE") (pin "3") (pinfunction "P1_3") (pintype "bidirectional"))
      (node (ref "IC4") (pin "1") (pinfunction "A_1") (pintype "input"))
      (node (ref "IC4") (pin "2") (pinfunction "B_2") (pintype "input"))
    )
    (net (code "39") (name "Net-(GAUGE-P2)") (class "Default")
      (node (ref "GAUGE") (pin "1") (pinfunction "P2_1") (pintype "bidirectional"))
      (node (ref "IC4") (pin "8") (pinfunction "CLK_8") (pintype "input"))
    )
    (net (code "40") (name "Net-(GAUGE-P3{slash}SDA)") (class "Default")
      (node (ref "GAUGE") (pin "8") (pinfunction "P3/SDA_8") (pintype "bidirectional"))
      (node (ref "I2C_SELECT") (pin "2") (pinfunction "2_2") (pintype "passive"))
    )
    (net (code "41") (name "Net-(GAUGE-P4{slash}SCL)") (class "Default")
      (node (ref "GAUGE") (pin "9") (pinfunction "P4/SCL_9") (pintype "bidirectional"))
      (node (ref "I2C_PGM") (pin "1") (pinfunction "S_1") (pintype "passive"))
      (node (ref "PROTECTION") (pin "27") (pinfunction "SCLK_27") (pintype "bidirectional"))
      (node (ref "R30") (pin "2") (pinfunction "2_2") (pintype "passive"))
    )
    (net (code "42") (name "Net-(GAUGE-REG25)") (class "Default")
      (node (ref "C33") (pin "1") (pinfunction "1_1") (pintype "passive"))
      (node (ref "GAUGE") (pin "7") (pinfunction "REG25_7") (pintype "bidirectional"))
      (node (ref "R49") (pin "1") (pinfunction "1_1") (pintype "passive"))
    )
    (net (code "43") (name "Net-(GAUGE-SRN)") (class "Default")
      (node (ref "C31") (pin "2") (pinfunction "2_2") (pintype "passive"))
      (node (ref "GAUGE") (pin "12") (pinfunction "SRN_12") (pintype "bidirectional"))
      (node (ref "R48") (pin "1") (pinfunction "1_1") (pintype "passive"))
    )
    (net (code "44") (name "Net-(GAUGE-SRP)") (class "Default")
      (node (ref "C32") (pin "2") (pinfunction "2_2") (pintype "passive"))
      (node (ref "GAUGE") (pin "13") (pinfunction "SRP_13") (pintype "bidirectional"))
      (node (ref "R47") (pin "1") (pinfunction "1_1") (pintype "passive"))
    )
    (net (code "45") (name "Net-(GAUGE-VEN)") (class "Default")
      (node (ref "GAUGE") (pin "2") (pinfunction "VEN_2") (pintype "bidirectional"))
      (node (ref "VIEW_SOC") (pin "P$3") (pinfunction "P$2_P$3") (pintype "bidirectional"))
      (node (ref "VIEW_SOC") (pin "P$4") (pinfunction "P$2_P$4") (pintype "bidirectional"))
    )
    (net (code "46") (name "Net-(I2C_PGMB-S)") (class "Default")
      (node (ref "I2C_PGM") (pin "2") (pinfunction "S_2") (pintype "passive"))
      (node (ref "I2C_SELECT") (pin "1") (pinfunction "1_1") (pintype "passive"))
      (node (ref "R29") (pin "2") (pinfunction "2_2") (pintype "passive"))
    )
    (net (code "47") (name "Net-(IC4A-QA)") (class "Default")
      (node (ref "IC4") (pin "3") (pinfunction "QA_3") (pintype "output"))
      (node (ref "SOC_LED1") (pin "C") (pinfunction "C_C") (pintype "passive"))
    )
    (net (code "48") (name "Net-(IC4A-QB)") (class "Default")
      (node (ref "IC4") (pin "4") (pinfunction "QB_4") (pintype "output"))
      (node (ref "SOC_LED2") (pin "C") (pinfunction "C_C") (pintype "passive"))
    )
    (net (code "49") (name "Net-(IC4A-QC)") (class "Default")
      (node (ref "IC4") (pin "5") (pinfunction "QC_5") (pintype "output"))
      (node (ref "SOC_LED3") (pin "C") (pinfunction "C_C") (pintype "passive"))
    )
    (net (code "50") (name "Net-(IC4A-QD)") (class "Default")
      (node (ref "IC4") (pin "6") (pinfunction "QD_6") (pintype "output"))
      (node (ref "SOC_LED4") (pin "C") (pinfunction "C_C") (pintype "passive"))
    )
    (net (code "51") (name "Net-(IC4A-QE)") (class "Default")
      (node (ref "IC4") (pin "10") (pinfunction "QE_10") (pintype "output"))
      (node (ref "SOC_LED5") (pin "C") (pinfunction "C_C") (pintype "passive"))
    )
    (net (code "52") (name "Net-(IC4A-QF)") (class "Default")
      (node (ref "IC4") (pin "11") (pinfunction "QF_11") (pintype "output"))
      (node (ref "SOC_LED6") (pin "C") (pinfunction "C_C") (pintype "passive"))
    )
    (net (code "53") (name "Net-(IC4A-QG)") (class "Default")
      (node (ref "IC4") (pin "12") (pinfunction "QG_12") (pintype "output"))
      (node (ref "SOC_LED7") (pin "C") (pinfunction "C_C") (pintype "passive"))
    )
    (net (code "54") (name "Net-(IC4A-QH)") (class "Default")
      (node (ref "IC4") (pin "13") (pinfunction "QH_13") (pintype "output"))
      (node (ref "SOC_LED8") (pin "C") (pinfunction "C_C") (pintype "passive"))
    )
    (net (code "55") (name "Net-(LED1-PadA)") (class "Default")
      (node (ref "LED1") (pin "A") (pinfunction "A_A") (pintype "passive"))
      (node (ref "R10") (pin "1") (pinfunction "1_1") (pintype "passive"))
    )
    (net (code "56") (name "Net-(LED2-PadA)") (class "Default")
      (node (ref "LED2") (pin "A") (pinfunction "A_A") (pintype "passive"))
      (node (ref "R13") (pin "1") (pinfunction "1_1") (pintype "passive"))
    )
    (net (code "57") (name "Net-(LED3-PadA)") (class "Default")
      (node (ref "LED3") (pin "A") (pinfunction "A_A") (pintype "passive"))
      (node (ref "R14") (pin "1") (pinfunction "1_1") (pintype "passive"))
    )
    (net (code "58") (name "Net-(PGM_PWRB-S)") (class "Default")
      (node (ref "PGM_PWR") (pin "2") (pinfunction "S_2") (pintype "passive"))
      (node (ref "PROTECTION") (pin "28") (pinfunction "EEPROM_28") (pintype "bidirectional"))
    )
    (net (code "59") (name "Net-(PROTECTION-BAT)") (class "Default")
      (node (ref "C34") (pin "1") (pinfunction "1_1") (pintype "passive"))
      (node (ref "C36") (pin "1") (pinfunction "1_1") (pintype "passive"))
      (node (ref "D2") (pin "C") (pinfunction "C_C") (pintype "passive"))
      (node (ref "PROTECTION") (pin "31") (pinfunction "BAT_31") (pintype "bidirectional"))
    )
    (net (code "60") (name "Net-(PROTECTION-CCAP)") (class "Default")
      (node (ref "CCCAP") (pin "2") (pinfunction "2_2") (pintype "passive"))
      (node (ref "PROTECTION") (pin "20") (pinfunction "CCAP_20") (pintype "bidirectional"))
    )
    (net (code "61") (name "Net-(PROTECTION-CHG)") (class "Default")
      (node (ref "PROTECTION") (pin "21") (pinfunction "CHG_21") (pintype "bidirectional"))
      (node (ref "Q8") (pin "1") (pinfunction "G_1") (pintype "passive"))
      (node (ref "R37") (pin "2") (pinfunction "2_2") (pintype "passive"))
    )
    (net (code "62") (name "Net-(PROTECTION-CPCKN)") (class "Default")
      (node (ref "PROTECTION") (pin "19") (pinfunction "CPCKN_19") (pintype "bidirectional"))
      (node (ref "RCPCKN") (pin "2") (pinfunction "2_2") (pintype "passive"))
    )
    (net (code "63") (name "Net-(PROTECTION-DCAP)") (class "Default")
      (node (ref "CDCAP") (pin "2") (pinfunction "2_2") (pintype "passive"))
      (node (ref "PROTECTION") (pin "16") (pinfunction "DCAP_16") (pintype "bidirectional"))
    )
    (net (code "64") (name "Net-(PROTECTION-DPCKN)") (class "Default")
      (node (ref "PROTECTION") (pin "18") (pinfunction "DPCKN_18") (pintype "bidirectional"))
      (node (ref "RDPCKN") (pin "2") (pinfunction "2_2") (pintype "passive"))
      (node (ref "RLDRM_DET") (pin "1") (pinfunction "1_1") (pintype "passive"))
    )
    (net (code "65") (name "Net-(PROTECTION-DSG)") (class "Default")
      (node (ref "PROTECTION") (pin "17") (pinfunction "DSG_17") (pintype "bidirectional"))
      (node (ref "R39") (pin "2") (pinfunction "2_2") (pintype "passive"))
    )
    (net (code "66") (name "Net-(PROTECTION-SDATA)") (class "Default")
      (node (ref "I2C_SELECT") (pin "3") (pinfunction "3_3") (pintype "passive"))
      (node (ref "PROTECTION") (pin "26") (pinfunction "SDATA_26") (pintype "bidirectional"))
    )
    (net (code "67") (name "Net-(PROTECTION-SENSE+)") (class "Default")
      (node (ref "C39") (pin "2") (pinfunction "2_2") (pintype "passive"))
      (node (ref "PROTECTION") (pin "10") (pinfunction "SENSE+_10") (pintype "bidirectional"))
      (node (ref "R45") (pin "1") (pinfunction "1_1") (pintype "passive"))
    )
    (net (code "68") (name "Net-(PROTECTION-SENSE-)") (class "Default")
      (node (ref "C40") (pin "2") (pinfunction "2_2") (pintype "passive"))
      (node (ref "PROTECTION") (pin "9") (pinfunction "SENSE-_9") (pintype "bidirectional"))
      (node (ref "R44") (pin "1") (pinfunction "1_1") (pintype "passive"))
    )
    (net (code "69") (name "Net-(PROTECTION-VC1)") (class "Default")
      (node (ref "PROTECTION") (pin "34") (pinfunction "VC1_34") (pintype "bidirectional"))
      (node (ref "R36") (pin "1") (pinfunction "1_1") (pintype "passive"))
    )
    (net (code "70") (name "Net-(PROTECTION-VC2)") (class "Default")
      (node (ref "CVC2") (pin "1") (pinfunction "1_1") (pintype "passive"))
      (node (ref "PROTECTION") (pin "36") (pinfunction "VC2_36") (pintype "bidirectional"))
      (node (ref "R36") (pin "2") (pinfunction "2_2") (pintype "passive"))
      (node (ref "RVC2") (pin "1") (pinfunction "1_1") (pintype "passive"))
    )
    (net (code "71") (name "Net-(PROTECTION-VC3)") (class "Default")
      (node (ref "CVC2") (pin "2") (pinfunction "2_2") (pintype "passive"))
      (node (ref "CVC3") (pin "1") (pinfunction "1_1") (pintype "passive"))
      (node (ref "PROTECTION") (pin "38") (pinfunction "VC3_38") (pintype "bidirectional"))
      (node (ref "RVC3") (pin "1") (pinfunction "1_1") (pintype "passive"))
    )
    (net (code "72") (name "Net-(PROTECTION-VC4)") (class "Default")
      (node (ref "CVC3") (pin "2") (pinfunction "2_2") (pintype "passive"))
      (node (ref "CVC4") (pin "1") (pinfunction "1_1") (pintype "passive"))
      (node (ref "PROTECTION") (pin "1") (pinfunction "VC4_1") (pintype "bidirectional"))
      (node (ref "RVC4") (pin "1") (pinfunction "1_1") (pintype "passive"))
    )
    (net (code "73") (name "Net-(PROTECTION-VC5)") (class "Default")
      (node (ref "CVC4") (pin "2") (pinfunction "2_2") (pintype "passive"))
      (node (ref "CVC5") (pin "1") (pinfunction "1_1") (pintype "passive"))
      (node (ref "PROTECTION") (pin "3") (pinfunction "VC5_3") (pintype "bidirectional"))
      (node (ref "RVC5") (pin "1") (pinfunction "1_1") (pintype "passive"))
    )
    (net (code "74") (name "Net-(PROTECTION-VC6)") (class "Default")
      (node (ref "CVC5") (pin "2") (pinfunction "2_2") (pintype "passive"))
      (node (ref "CVC6") (pin "1") (pinfunction "1_1") (pintype "passive"))
      (node (ref "PROTECTION") (pin "5") (pinfunction "VC6_5") (pintype "bidirectional"))
      (node (ref "RVC6") (pin "1") (pinfunction "1_1") (pintype "passive"))
    )
    (net (code "75") (name "Net-(PROTECTION-VC7)") (class "Default")
      (node (ref "CVC6") (pin "2") (pinfunction "2_2") (pintype "passive"))
      (node (ref "CVC7") (pin "1") (pinfunction "1_1") (pintype "passive"))
      (node (ref "PROTECTION") (pin "6") (pinfunction "VC7_6") (pintype "bidirectional"))
      (node (ref "RVC7") (pin "1") (pinfunction "1_1") (pintype "passive"))
    )
    (net (code "76") (name "Net-(PROTECTION-VC8)") (class "Default")
      (node (ref "CVC7") (pin "2") (pinfunction "2_2") (pintype "passive"))
      (node (ref "CVC8") (pin "1") (pinfunction "1_1") (pintype "passive"))
      (node (ref "PROTECTION") (pin "7") (pinfunction "VC8_7") (pintype "bidirectional"))
      (node (ref "RVC8") (pin "1") (pinfunction "1_1") (pintype "passive"))
    )
    (net (code "77") (name "Net-(PROTECTION-VC9)") (class "Default")
      (node (ref "CVC8") (pin "2") (pinfunction "2_2") (pintype "passive"))
      (node (ref "PROTECTION") (pin "8") (pinfunction "VC9_8") (pintype "bidirectional"))
      (node (ref "RVC9") (pin "1") (pinfunction "1_1") (pintype "passive"))
    )
    (net (code "78") (name "Net-(PROTECTION-VREG)") (class "Default")
      (node (ref "CVREG") (pin "2") (pinfunction "2_2") (pintype "passive"))
      (node (ref "PGM_ENABLE") (pin "1") (pinfunction "1_1") (pintype "passive"))
      (node (ref "PROTECTION") (pin "12") (pinfunction "VREG_12") (pintype "bidirectional"))
      (node (ref "R29") (pin "1") (pinfunction "1_1") (pintype "passive"))
      (node (ref "R30") (pin "1") (pinfunction "1_1") (pintype "passive"))
    )
    (net (code "79") (name "Net-(PROTECTION-ZEDE)") (class "Default")
      (node (ref "PGM_ENABLE") (pin "2") (pinfunction "2_2") (pintype "passive"))
      (node (ref "PROTECTION") (pin "22") (pinfunction "ZEDE_22") (pintype "bidirectional"))
    )
    (net (code "80") (name "Net-(Q3-G)") (class "Default")
      (node (ref "C12") (pin "2") (pinfunction "2_2") (pintype "passive"))
      (node (ref "Q3") (pin "1") (pinfunction "G_1") (pintype "passive"))
      (node (ref "Q4") (pin "1") (pinfunction "G_1") (pintype "passive"))
      (node (ref "R4") (pin "1") (pinfunction "1_1") (pintype "passive"))
      (node (ref "R5") (pin "2") (pinfunction "2_2") (pintype "passive"))
    )
    (net (code "81") (name "Net-(Q3-S)") (class "Default")
      (node (ref "C12") (pin "1") (pinfunction "1_1") (pintype "passive"))
      (node (ref "Q3") (pin "2") (pinfunction "S_2") (pintype "passive"))
      (node (ref "Q4") (pin "2") (pinfunction "S_2") (pintype "passive"))
      (node (ref "R4") (pin "2") (pinfunction "2_2") (pintype "passive"))
      (node (ref "R9") (pin "2") (pinfunction "2_2") (pintype "passive"))
    )
    (net (code "82") (name "Net-(Q5-G)") (class "Default")
      (node (ref "C21") (pin "2") (pinfunction "2_2") (pintype "passive"))
      (node (ref "Q5") (pin "1") (pinfunction "G_1") (pintype "passive"))
      (node (ref "R23") (pin "2") (pinfunction "2_2") (pintype "passive"))
      (node (ref "R24") (pin "2") (pinfunction "2_2") (pintype "passive"))
    )
    (net (code "83") (name "Net-(Q8-D)") (class "Default")
      (node (ref "Q8") (pin "3") (pinfunction "D_3") (pintype "passive"))
      (node (ref "Q9") (pin "3") (pinfunction "D_3") (pintype "passive"))
      (node (ref "RDPCKN") (pin "1") (pinfunction "1_1") (pintype "passive"))
    )
    (net (code "84") (name "Net-(Q9-G)") (class "Default")
      (node (ref "Q9") (pin "1") (pinfunction "G_1") (pintype "passive"))
      (node (ref "R38") (pin "2") (pinfunction "2_2") (pintype "passive"))
      (node (ref "R39") (pin "1") (pinfunction "1_1") (pintype "passive"))
    )
    (net (code "85") (name "Net-(Q9-S)") (class "Default")
      (node (ref "Q9") (pin "2") (pinfunction "S_2") (pintype "passive"))
      (node (ref "R38") (pin "1") (pinfunction "1_1") (pintype "passive"))
      (node (ref "R43") (pin "1") (pinfunction "1_1") (pintype "passive"))
      (node (ref "R47") (pin "2") (pinfunction "2_2") (pintype "passive"))
    )
    (net (code "86") (name "Net-(R31-Pad1)") (class "Default")
      (node (ref "R31") (pin "1") (pinfunction "1_1") (pintype "passive"))
      (node (ref "SOC_LED1") (pin "A") (pinfunction "A_A") (pintype "passive"))
    )
    (net (code "87") (name "Net-(R32-Pad1)") (class "Default")
      (node (ref "R32") (pin "1") (pinfunction "1_1") (pintype "passive"))
      (node (ref "SOC_LED2") (pin "A") (pinfunction "A_A") (pintype "passive"))
    )
    (net (code "88") (name "Net-(R33-Pad1)") (class "Default")
      (node (ref "R33") (pin "1") (pinfunction "1_1") (pintype "passive"))
      (node (ref "SOC_LED3") (pin "A") (pinfunction "A_A") (pintype "passive"))
    )
    (net (code "89") (name "Net-(R34-Pad1)") (class "Default")
      (node (ref "R34") (pin "1") (pinfunction "1_1") (pintype "passive"))
      (node (ref "SOC_LED4") (pin "A") (pinfunction "A_A") (pintype "passive"))
    )
    (net (code "90") (name "Net-(R35-Pad1)") (class "Default")
      (node (ref "R35") (pin "1") (pinfunction "1_1") (pintype "passive"))
      (node (ref "SOC_LED5") (pin "A") (pinfunction "A_A") (pintype "passive"))
    )
    (net (code "91") (name "Net-(R40-Pad1)") (class "Default")
      (node (ref "R40") (pin "1") (pinfunction "1_1") (pintype "passive"))
      (node (ref "SOC_LED6") (pin "A") (pinfunction "A_A") (pintype "passive"))
    )
    (net (code "92") (name "Net-(R41-Pad1)") (class "Default")
      (node (ref "R41") (pin "1") (pinfunction "1_1") (pintype "passive"))
      (node (ref "SOC_LED7") (pin "A") (pinfunction "A_A") (pintype "passive"))
    )
    (net (code "93") (name "Net-(R42-Pad1)") (class "Default")
      (node (ref "R42") (pin "1") (pinfunction "1_1") (pintype "passive"))
      (node (ref "SOC_LED8") (pin "A") (pinfunction "A_A") (pintype "passive"))
    )
    (net (code "94") (name "Net-(R43-Pad2)") (class "Default")
      (node (ref "R43") (pin "2") (pinfunction "2_2") (pintype "passive"))
      (node (ref "R45") (pin "2") (pinfunction "2_2") (pintype "passive"))
      (node (ref "R46") (pin "1") (pinfunction "1_1") (pintype "passive"))
      (node (ref "R48") (pin "2") (pinfunction "2_2") (pintype "passive"))
    )
    (net (code "95") (name "Net-(R49-Pad2)") (class "Default")
      (node (ref "R49") (pin "2") (pinfunction "2_2") (pintype "passive"))
      (node (ref "VIEW_SOC") (pin "P$1") (pinfunction "P$1_P$1") (pintype "bidirectional"))
      (node (ref "VIEW_SOC") (pin "P$2") (pinfunction "P$1_P$2") (pintype "bidirectional"))
    )
    (net (code "96") (name "unconnected-(GAUGE-P5{slash}HDQ-Pad10)") (class "Default")
      (node (ref "GAUGE") (pin "10") (pinfunction "P5/HDQ_10") (pintype "bidirectional"))
    )
    (net (code "97") (name "unconnected-(GAUGE-P6{slash}TS-Pad11)") (class "Default")
      (node (ref "GAUGE") (pin "11") (pinfunction "P6/TS_11") (pintype "bidirectional"))
    )
    (net (code "98") (name "unconnected-(PROTECTION-VTSB-Pad15)") (class "Default")
      (node (ref "PROTECTION") (pin "15") (pinfunction "VTSB_15") (pintype "bidirectional"))
    )
  )
)
